# PE02.net
KiCad netlist of a schematic drawn in EAGLE
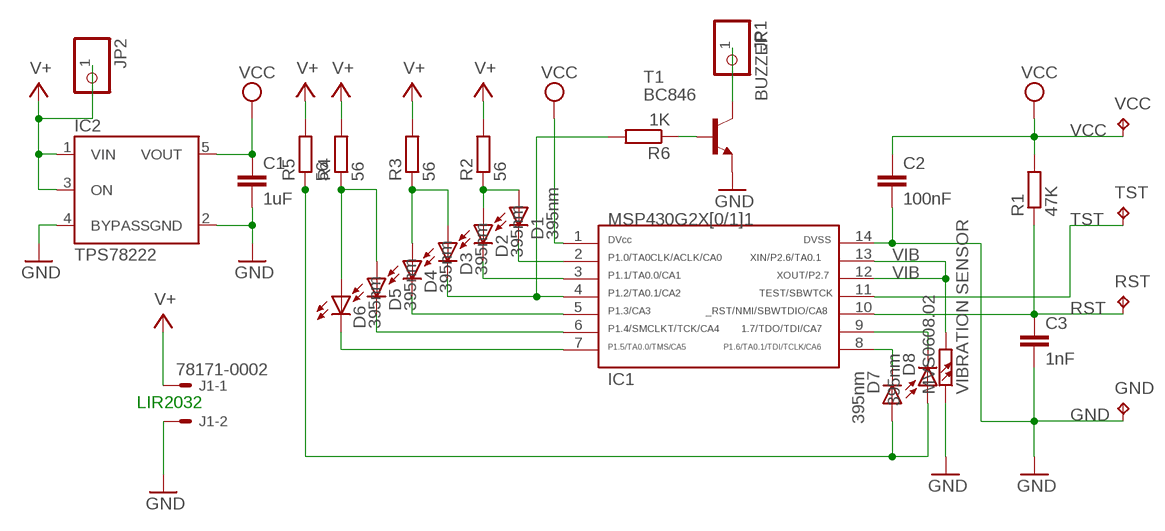
[diagram p0: schematic, sheet 1]

(export (version "E")
  (design (tool "Eeschema 10.0.6"))
  (components
    (comp (ref "C1")
      (value "1uF")
      (footprint "eagle-import:0805")
      (libsource (lib "eagle-import") (part "CAP0805"))
    )
    (comp (ref "C2")
      (value "100nF")
      (footprint "eagle-import:0805")
      (libsource (lib "eagle-import") (part "CAP0805"))
    )
    (comp (ref "C3")
      (value "1nF")
      (footprint "eagle-import:0805")
      (libsource (lib "eagle-import") (part "CAP0805"))
    )
    (comp (ref "D1")
      (value "395nm")
      (footprint "eagle-import:LED-3MM")
      (libsource (lib "eagle-import") (part "LED-3MM"))
    )
    (comp (ref "D2")
      (value "395nm")
      (footprint "eagle-import:LED-3MM")
      (libsource (lib "eagle-import") (part "LED-3MM"))
    )
    (comp (ref "D3")
      (value "395nm")
      (footprint "eagle-import:LED-3MM")
      (libsource (lib "eagle-import") (part "LED-3MM"))
    )
    (comp (ref "D4")
      (value "395nm")
      (footprint "eagle-import:LED-3MM")
      (libsource (lib "eagle-import") (part "LED-3MM"))
    )
    (comp (ref "D5")
      (value "395nm")
      (footprint "eagle-import:LED-3MM")
      (libsource (lib "eagle-import") (part "LED-3MM"))
    )
    (comp (ref "D6")
      (value "395nm")
      (footprint "eagle-import:LED-3MM")
      (libsource (lib "eagle-import") (part "LED-3MM"))
    )
    (comp (ref "D7")
      (value "395nm")
      (footprint "eagle-import:LED-3MM")
      (libsource (lib "eagle-import") (part "LED-3MM"))
    )
    (comp (ref "D8")
      (value "395nm")
      (footprint "eagle-import:LED-3MM")
      (libsource (lib "eagle-import") (part "LED-3MM"))
    )
    (comp (ref "GND")
      (value "TPTP10R")
      (footprint "eagle-import:TP10R")
      (libsource (lib "eagle-import") (part "TPTP10R"))
    )
    (comp (ref "IC1")
      (value "MSP430G2231")
      (footprint "eagle-import:PW14")
      (libsource (lib "eagle-import") (part "G2X[0/1]1---PW14"))
    )
    (comp (ref "IC2")
      (value "TPS78222")
      (footprint "eagle-import:SOT23-5")
      (libsource (lib "eagle-import") (part "LP2982M5"))
    )
    (comp (ref "J1")
      (value "78171-0002")
      (footprint "eagle-import:78171-0002")
      (libsource (lib "eagle-import") (part "78171-0002"))
    )
    (comp (ref "JP1")
      (value "PINHD-1X1CB")
      (footprint "eagle-import:1X01-CLEANBIG")
      (libsource (lib "eagle-import") (part "PINHD-1X1CB"))
    )
    (comp (ref "JP2")
      (value "PINHD-1X1CB")
      (footprint "eagle-import:1X01-CLEANBIG")
      (libsource (lib "eagle-import") (part "PINHD-1X1CB"))
    )
    (comp (ref "MVS0608.02")
      (value "VIBRATION SENSOR")
      (footprint "eagle-import:R1210")
      (libsource (lib "eagle-import") (part "R-EU_R1210"))
    )
    (comp (ref "R1")
      (value "47K")
      (footprint "eagle-import:R0603")
      (libsource (lib "eagle-import") (part "R-EU_R0603"))
    )
    (comp (ref "R2")
      (value "56")
      (footprint "eagle-import:R0603")
      (libsource (lib "eagle-import") (part "R-EU_R0603"))
    )
    (comp (ref "R3")
      (value "56")
      (footprint "eagle-import:R0603")
      (libsource (lib "eagle-import") (part "R-EU_R0603"))
    )
    (comp (ref "R4")
      (value "56")
      (footprint "eagle-import:R0603")
      (libsource (lib "eagle-import") (part "R-EU_R0603"))
    )
    (comp (ref "R5")
      (value "56")
      (footprint "eagle-import:R0603")
      (libsource (lib "eagle-import") (part "R-EU_R0603"))
    )
    (comp (ref "R6")
      (value "1K")
      (footprint "eagle-import:R0603")
      (libsource (lib "eagle-import") (part "R-EU_R0603"))
    )
    (comp (ref "RST")
      (value "TPTP10R")
      (footprint "eagle-import:TP10R")
      (libsource (lib "eagle-import") (part "TPTP10R"))
    )
    (comp (ref "T1")
      (value "BC846")
      (footprint "eagle-import:SOT23")
      (libsource (lib "eagle-import") (part "BC846"))
    )
    (comp (ref "TST")
      (value "TPTP10R")
      (footprint "eagle-import:TP10R")
      (libsource (lib "eagle-import") (part "TPTP10R"))
    )
    (comp (ref "VCC")
      (value "TPTP10R")
      (footprint "eagle-import:TP10R")
      (libsource (lib "eagle-import") (part "TPTP10R"))
    )
  )
  (nets
    (net (code "1") (name "/BUZZER") (class "Default")
      (node (ref "JP1") (pin "1") (pinfunction "1_1") (pintype "passive"))
      (node (ref "T1") (pin "3") (pinfunction "C_3") (pintype "passive"))
    )
    (net (code "2") (name "/RST") (class "Default")
      (node (ref "C3") (pin "1") (pinfunction "1_1") (pintype "passive"))
      (node (ref "IC1") (pin "10") (pinfunction "10_10") (pintype "bidirectional"))
      (node (ref "R1") (pin "1") (pinfunction "1_1") (pintype "passive"))
      (node (ref "RST") (pin "TP") (pinfunction "TP_TP") (pintype "input"))
    )
    (net (code "3") (name "/TST") (class "Default")
      (node (ref "IC1") (pin "11") (pinfunction "11_11") (pintype "bidirectional"))
      (node (ref "TST") (pin "TP") (pinfunction "TP_TP") (pintype "input"))
    )
    (net (code "4") (name "/VIB") (class "Default")
      (node (ref "IC1") (pin "12") (pinfunction "12_12") (pintype "bidirectional"))
      (node (ref "IC1") (pin "13") (pinfunction "13_13") (pintype "bidirectional"))
      (node (ref "MVS0608.02") (pin "2") (pinfunction "2_2") (pintype "passive"))
    )
    (net (code "5") (name "GND") (class "Default")
      (node (ref "C1") (pin "2") (pinfunction "2_2") (pintype "passive"))
      (node (ref "C2") (pin "2") (pinfunction "2_2") (pintype "passive"))
      (node (ref "C3") (pin "2") (pinfunction "2_2") (pintype "passive"))
      (node (ref "GND") (pin "TP") (pinfunction "TP_TP") (pintype "input"))
      (node (ref "IC1") (pin "14") (pinfunction "14_14") (pintype "bidirectional"))
      (node (ref "IC2") (pin "2") (pinfunction "GND_2") (pintype "power_in"))
      (node (ref "IC2") (pin "4") (pinfunction "BYPASS_4") (pintype "passive"))
      (node (ref "J1") (pin "2") (pinfunction "S_2") (pintype "passive"))
      (node (ref "MVS0608.02") (pin "1") (pinfunction "1_1") (pintype "passive"))
      (node (ref "T1") (pin "2") (pinfunction "E_2") (pintype "passive"))
    )
    (net (code "6") (name "Net-(D1-C)") (class "Default")
      (node (ref "D1") (pin "K") (pinfunction "C_K") (pintype "passive"))
      (node (ref "IC1") (pin "2") (pinfunction "2_2") (pintype "bidirectional"))
    )
    (net (code "7") (name "Net-(D1-PadA)") (class "Default")
      (node (ref "D1") (pin "A") (pinfunction "A_A") (pintype "passive"))
      (node (ref "D2") (pin "A") (pinfunction "A_A") (pintype "passive"))
      (node (ref "R2") (pin "1") (pinfunction "1_1") (pintype "passive"))
    )
    (net (code "8") (name "Net-(D2-C)") (class "Default")
      (node (ref "D2") (pin "K") (pinfunction "C_K") (pintype "passive"))
      (node (ref "IC1") (pin "3") (pinfunction "3_3") (pintype "bidirectional"))
    )
    (net (code "9") (name "Net-(D3-C)") (class "Default")
      (node (ref "D3") (pin "K") (pinfunction "C_K") (pintype "passive"))
      (node (ref "IC1") (pin "4") (pinfunction "4_4") (pintype "bidirectional"))
      (node (ref "R6") (pin "2") (pinfunction "2_2") (pintype "passive"))
    )
    (net (code "10") (name "Net-(D3-PadA)") (class "Default")
      (node (ref "D3") (pin "A") (pinfunction "A_A") (pintype "passive"))
      (node (ref "D4") (pin "A") (pinfunction "A_A") (pintype "passive"))
      (node (ref "R3") (pin "1") (pinfunction "1_1") (pintype "passive"))
    )
    (net (code "11") (name "Net-(D4-C)") (class "Default")
      (node (ref "D4") (pin "K") (pinfunction "C_K") (pintype "passive"))
      (node (ref "IC1") (pin "5") (pinfunction "5_5") (pintype "bidirectional"))
    )
    (net (code "12") (name "Net-(D5-C)") (class "Default")
      (node (ref "D5") (pin "K") (pinfunction "C_K") (pintype "passive"))
      (node (ref "IC1") (pin "6") (pinfunction "6_6") (pintype "bidirectional"))
    )
    (net (code "13") (name "Net-(D5-PadA)") (class "Default")
      (node (ref "D5") (pin "A") (pinfunction "A_A") (pintype "passive"))
      (node (ref "D6") (pin "A") (pinfunction "A_A") (pintype "passive"))
      (node (ref "R4") (pin "1") (pinfunction "1_1") (pintype "passive"))
    )
    (net (code "14") (name "Net-(D6-C)") (class "Default")
      (node (ref "D6") (pin "K") (pinfunction "C_K") (pintype "passive"))
      (node (ref "IC1") (pin "7") (pinfunction "7_7") (pintype "bidirectional"))
    )
    (net (code "15") (name "Net-(D7-C)") (class "Default")
      (node (ref "D7") (pin "K") (pinfunction "C_K") (pintype "passive"))
      (node (ref "IC1") (pin "8") (pinfunction "8_8") (pintype "bidirectional"))
    )
    (net (code "16") (name "Net-(D7-PadA)") (class "Default")
      (node (ref "D7") (pin "A") (pinfunction "A_A") (pintype "passive"))
      (node (ref "D8") (pin "A") (pinfunction "A_A") (pintype "passive"))
      (node (ref "R5") (pin "1") (pinfunction "1_1") (pintype "passive"))
    )
    (net (code "17") (name "Net-(D8-C)") (class "Default")
      (node (ref "D8") (pin "K") (pinfunction "C_K") (pintype "passive"))
      (node (ref "IC1") (pin "9") (pinfunction "9_9") (pintype "bidirectional"))
    )
    (net (code "18") (name "Net-(T1-B)") (class "Default")
      (node (ref "R6") (pin "1") (pinfunction "1_1") (pintype "passive"))
      (node (ref "T1") (pin "1") (pinfunction "B_1") (pintype "passive"))
    )
    (net (code "19") (name "V+") (class "Default")
      (node (ref "IC2") (pin "1") (pinfunction "VIN_1") (pintype "power_in"))
      (node (ref "IC2") (pin "3") (pinfunction "ON_3") (pintype "input"))
      (node (ref "J1") (pin "1") (pinfunction "S_1") (pintype "passive"))
      (node (ref "JP2") (pin "1") (pinfunction "1_1") (pintype "passive"))
      (node (ref "R2") (pin "2") (pinfunction "2_2") (pintype "passive"))
      (node (ref "R3") (pin "2") (pinfunction "2_2") (pintype "passive"))
      (node (ref "R4") (pin "2") (pinfunction "2_2") (pintype "passive"))
      (node (ref "R5") (pin "2") (pinfunction "2_2") (pintype "passive"))
    )
    (net (code "20") (name "VCC") (class "Default")
      (node (ref "C1") (pin "1") (pinfunction "1_1") (pintype "passive"))
      (node (ref "C2") (pin "1") (pinfunction "1_1") (pintype "passive"))
      (node (ref "IC1") (pin "1") (pinfunction "1_1") (pintype "bidirectional"))
      (node (ref "IC2") (pin "5") (pinfunction "VOUT_5") (pintype "output"))
      (node (ref "R1") (pin "2") (pinfunction "2_2") (pintype "passive"))
      (node (ref "VCC") (pin "TP") (pinfunction "TP_TP") (pintype "input"))
    )
  )
)
